# Sheet1.net
KiCad netlist of a schematic drawn in Altium Designer
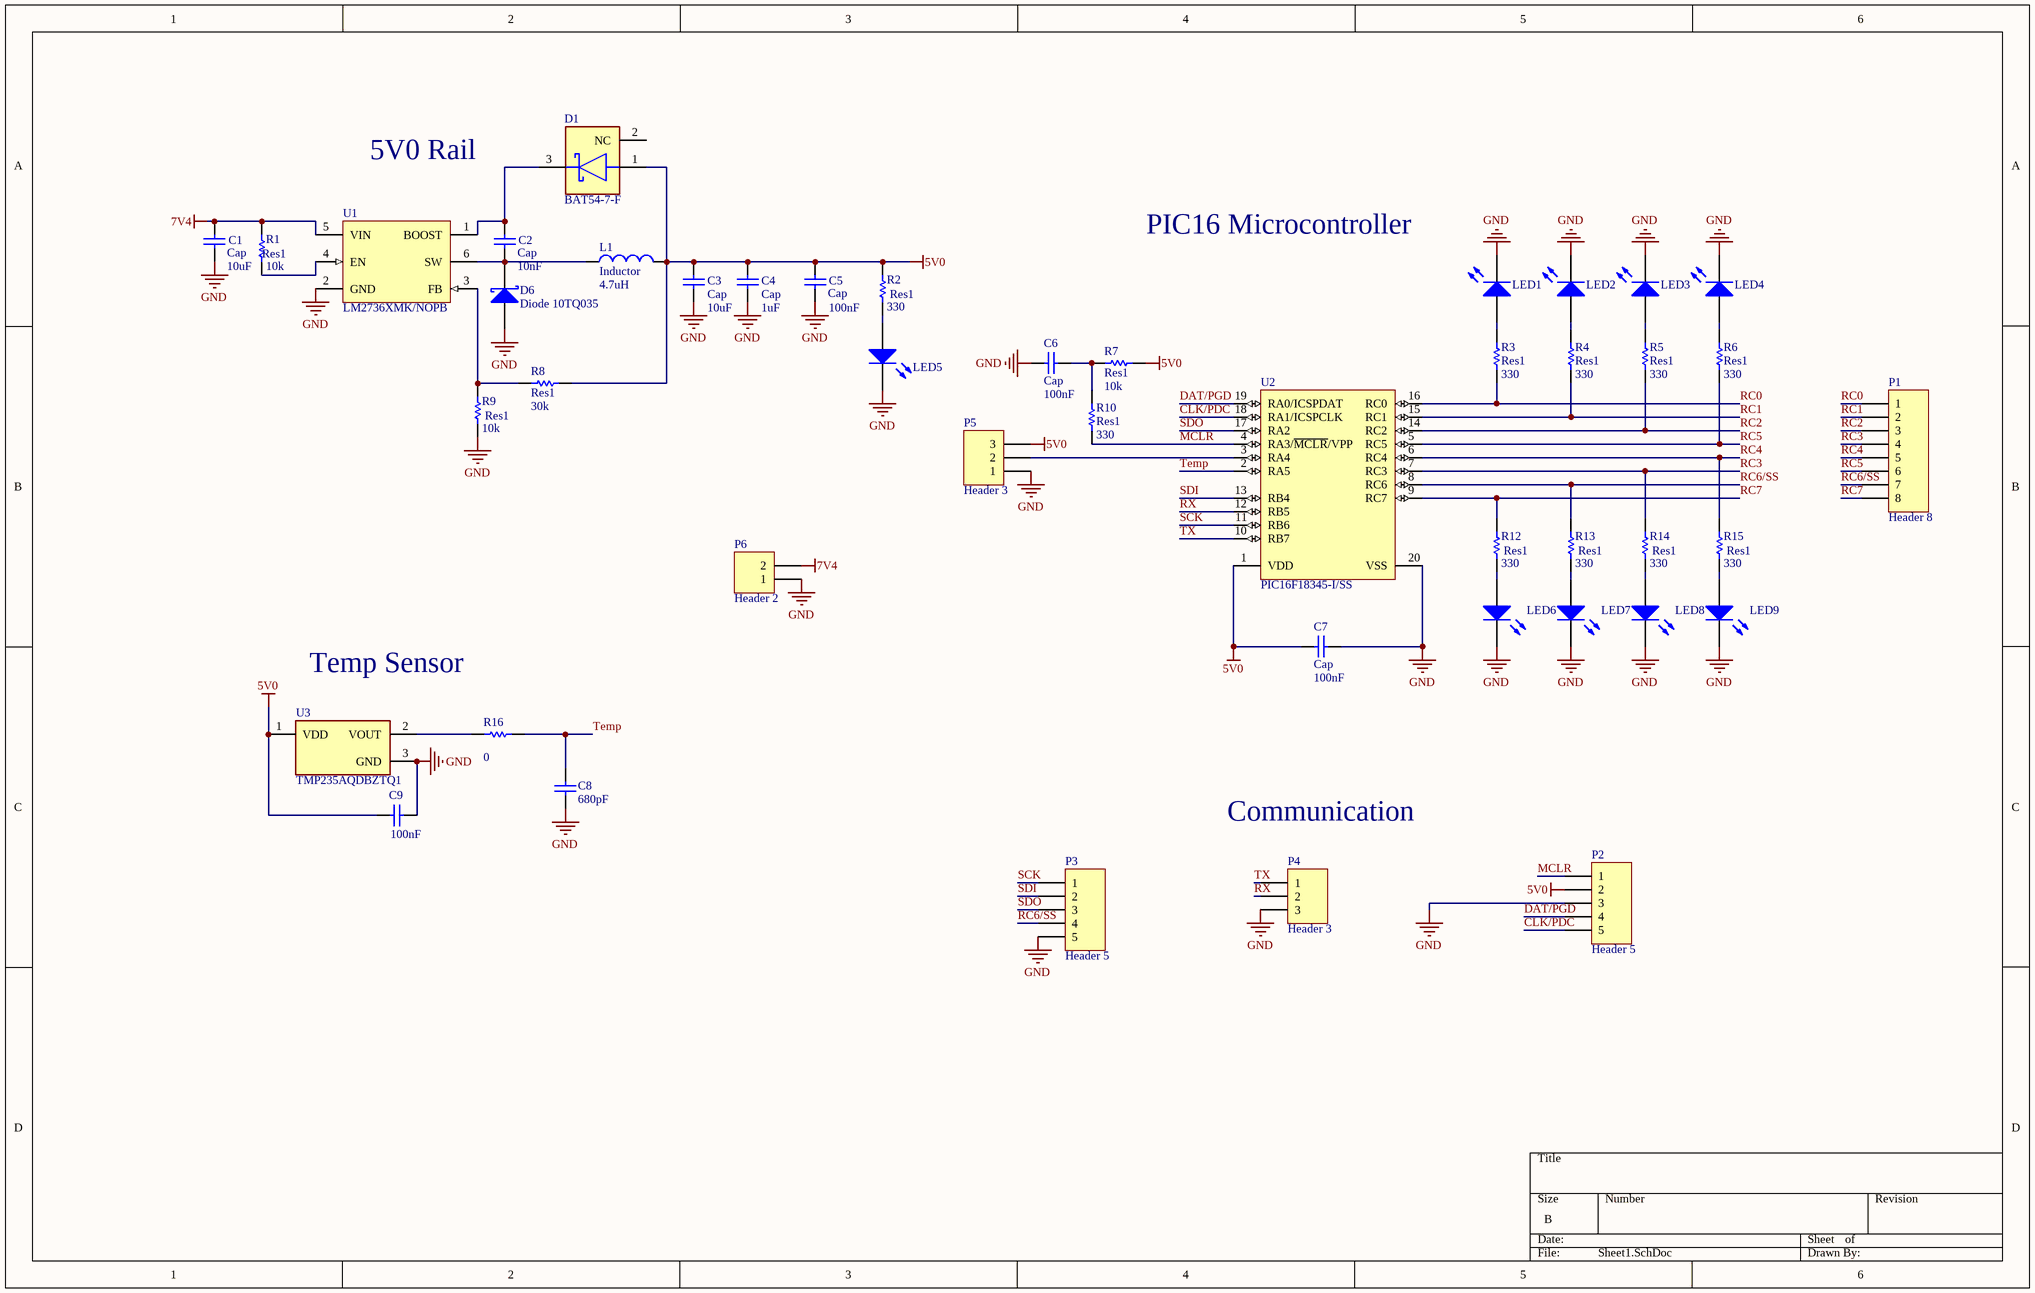
[diagram p0: Sheet1.SchDoc]

(export (version "E")
  (design (tool "Eeschema 10.0.6"))
  (components
    (comp (ref "C1")
      (value "Cap")
      (footprint "6-0805_M")
      (description "Capacitor")
      (fields (field (name "ALTIUM_VALUE") "10uF") (field (name "PUBLISHER") "Altium Limited"))
      (libsource (lib "Miscellaneous Devices") (part "Cap"))
    )
    (comp (ref "C2")
      (value "Cap")
      (footprint "6-0805_M")
      (description "Capacitor")
      (fields (field (name "ALTIUM_VALUE") "10nF") (field (name "PUBLISHER") "Altium Limited"))
      (libsource (lib "Miscellaneous Devices") (part "Cap"))
    )
    (comp (ref "C3")
      (value "Cap")
      (footprint "6-0805_M")
      (description "Capacitor")
      (fields (field (name "ALTIUM_VALUE") "10uF") (field (name "PUBLISHER") "Altium Limited"))
      (libsource (lib "Miscellaneous Devices") (part "Cap"))
    )
    (comp (ref "C4")
      (value "Cap")
      (footprint "6-0805_M")
      (description "Capacitor")
      (fields (field (name "ALTIUM_VALUE") "1uF") (field (name "PUBLISHER") "Altium Limited"))
      (libsource (lib "Miscellaneous Devices") (part "Cap"))
    )
    (comp (ref "C5")
      (value "Cap")
      (footprint "6-0805_M")
      (description "Capacitor")
      (fields (field (name "ALTIUM_VALUE") "100nF") (field (name "PUBLISHER") "Altium Limited"))
      (libsource (lib "Miscellaneous Devices") (part "Cap"))
    )
    (comp (ref "C6")
      (value "Cap")
      (footprint "6-0805_M")
      (description "Capacitor")
      (fields (field (name "ALTIUM_VALUE") "100nF") (field (name "PUBLISHER") "Altium Limited"))
      (libsource (lib "Miscellaneous Devices") (part "Cap"))
    )
    (comp (ref "C7")
      (value "Cap")
      (footprint "6-0805_M")
      (description "Capacitor")
      (fields (field (name "ALTIUM_VALUE") "100nF") (field (name "PUBLISHER") "Altium Limited"))
      (libsource (lib "Miscellaneous Devices") (part "Cap"))
    )
    (comp (ref "C8")
      (value "680pF")
      (footprint "6-0805_M")
      (description "Capacitor")
      (fields (field (name "Comment") "Cap") (field (name "PUBLISHER") "Altium Limited"))
      (libsource (lib "Miscellaneous Devices") (part "Cap"))
    )
    (comp (ref "C9")
      (value "100nF")
      (footprint "6-0805_M")
      (description "Capacitor")
      (fields (field (name "Comment") "Cap") (field (name "PUBLISHER") "Altium Limited"))
      (libsource (lib "Miscellaneous Devices") (part "Cap"))
    )
    (comp (ref "D1")
      (value "BAT54-7-F")
      (footprint "FP-SOT23-MFG")
      (description "DIODE SCHOTTKY 30V 200MA SOT23-3")
      (fields
        (field (name "MANUFACTURER") "Diodes Inc.")
        (field (name "OCTOPART") "https://octopart.com/bat54-7-f-diodes+inc.-39681803")
      )
      (libsource (lib "Altium Content Vault") (part "c46c961685e925f3e7b53c7fd0df730"))
    )
    (comp (ref "D6")
      (value "Diode 10TQ035")
      (footprint "CDBA5")
      (description "Schottky Rectifier")
      (fields (field (name "PUBLISHER") "Altium Limited"))
      (libsource (lib "Miscellaneous Devices") (part "Diode 10TQ035"))
    )
    (comp (ref "L1")
      (value "Inductor")
      (footprint "INDC2520X100N")
      (fields (field (name "ALTIUM_VALUE") "4.7uH") (field (name "PUBLISHER") "Altium Limited"))
      (libsource (lib "Miscellaneous Devices") (part "Inductor"))
    )
    (comp (ref "LED1")
      (value "150080BS75000")
      (footprint "0805_A")
      (description "SMD mono-color Chip LED, WL-SMCW, Blue")
      (fields (field (name "MANUFACTURER") "Wuerth Elektronik"))
      (libsource (lib "Altium Content Vault") (part "WE-LED_K1A2-2"))
    )
    (comp (ref "LED2")
      (value "150080BS75000")
      (footprint "0805_A")
      (description "SMD mono-color Chip LED, WL-SMCW, Blue")
      (fields (field (name "MANUFACTURER") "Wuerth Elektronik"))
      (libsource (lib "Altium Content Vault") (part "WE-LED_K1A2-2"))
    )
    (comp (ref "LED3")
      (value "150080BS75000")
      (footprint "0805_A")
      (description "SMD mono-color Chip LED, WL-SMCW, Blue")
      (fields (field (name "MANUFACTURER") "Wuerth Elektronik"))
      (libsource (lib "Altium Content Vault") (part "WE-LED_K1A2-2"))
    )
    (comp (ref "LED4")
      (value "150080BS75000")
      (footprint "0805_A")
      (description "SMD mono-color Chip LED, WL-SMCW, Blue")
      (fields (field (name "MANUFACTURER") "Wuerth Elektronik"))
      (libsource (lib "Altium Content Vault") (part "WE-LED_K1A2-2"))
    )
    (comp (ref "LED5")
      (value "150080BS75000")
      (footprint "0805_A")
      (description "SMD mono-color Chip LED, WL-SMCW, Blue")
      (fields (field (name "MANUFACTURER") "Wuerth Elektronik"))
      (libsource (lib "Altium Content Vault") (part "WE-LED_K1A2-2"))
    )
    (comp (ref "LED6")
      (value "150080BS75000")
      (footprint "0805_A")
      (description "SMD mono-color Chip LED, WL-SMCW, Blue")
      (fields (field (name "MANUFACTURER") "Wuerth Elektronik"))
      (libsource (lib "Altium Content Vault") (part "WE-LED_K1A2-2"))
    )
    (comp (ref "LED7")
      (value "150080BS75000")
      (footprint "0805_A")
      (description "SMD mono-color Chip LED, WL-SMCW, Blue")
      (fields (field (name "MANUFACTURER") "Wuerth Elektronik"))
      (libsource (lib "Altium Content Vault") (part "WE-LED_K1A2-2"))
    )
    (comp (ref "LED8")
      (value "150080BS75000")
      (footprint "0805_A")
      (description "SMD mono-color Chip LED, WL-SMCW, Blue")
      (fields (field (name "MANUFACTURER") "Wuerth Elektronik"))
      (libsource (lib "Altium Content Vault") (part "WE-LED_K1A2-2"))
    )
    (comp (ref "LED9")
      (value "150080BS75000")
      (footprint "0805_A")
      (description "SMD mono-color Chip LED, WL-SMCW, Blue")
      (fields (field (name "MANUFACTURER") "Wuerth Elektronik"))
      (libsource (lib "Altium Content Vault") (part "WE-LED_K1A2-2"))
    )
    (comp (ref "P1")
      (value "Header 8")
      (footprint "HDR1X8")
      (description "Header, 8-Pin")
      (fields (field (name "PUBLISHER") "Altium Limited"))
      (libsource (lib "Miscellaneous Connectors") (part "Header 8"))
    )
    (comp (ref "P2")
      (value "Header 5")
      (footprint "HDR1X5")
      (description "Header, 5-Pin")
      (fields (field (name "PUBLISHER") "Altium Limited"))
      (libsource (lib "Miscellaneous Connectors") (part "Header 5"))
    )
    (comp (ref "P3")
      (value "Header 5")
      (footprint "HDR1X5")
      (description "Header, 5-Pin")
      (fields (field (name "PUBLISHER") "Altium Limited"))
      (libsource (lib "Miscellaneous Connectors") (part "Header 5"))
    )
    (comp (ref "P4")
      (value "Header 3")
      (footprint "HDR1X3")
      (description "Header, 3-Pin")
      (fields (field (name "PUBLISHER") "Altium Limited"))
      (libsource (lib "") (part "Header 3_1"))
    )
    (comp (ref "P5")
      (value "Header 3")
      (footprint "HDR1X3")
      (description "Header, 3-Pin")
      (fields (field (name "PUBLISHER") "Altium Limited"))
      (libsource (lib "Miscellaneous Connectors") (part "Header 3"))
    )
    (comp (ref "P6")
      (value "Header 2")
      (footprint "HDR1X2")
      (description "Header, 2-Pin")
      (fields (field (name "PUBLISHER") "Altium Limited"))
      (libsource (lib "Miscellaneous Connectors") (part "Header 2"))
    )
    (comp (ref "R1")
      (value "Res1")
      (footprint "6-0805_M")
      (description "Resistor")
      (fields (field (name "ALTIUM_VALUE") "10k") (field (name "PUBLISHER") "Altium Limited"))
      (libsource (lib "Miscellaneous Devices") (part "Res1"))
    )
    (comp (ref "R2")
      (value "Res1")
      (footprint "6-0805_M")
      (description "Resistor")
      (fields (field (name "ALTIUM_VALUE") "330") (field (name "PUBLISHER") "Altium Limited"))
      (libsource (lib "Miscellaneous Devices") (part "Res1"))
    )
    (comp (ref "R3")
      (value "Res1")
      (footprint "6-0805_M")
      (description "Resistor")
      (fields (field (name "ALTIUM_VALUE") "330") (field (name "PUBLISHER") "Altium Limited"))
      (libsource (lib "Miscellaneous Devices") (part "Res1"))
    )
    (comp (ref "R4")
      (value "Res1")
      (footprint "6-0805_M")
      (description "Resistor")
      (fields (field (name "ALTIUM_VALUE") "330") (field (name "PUBLISHER") "Altium Limited"))
      (libsource (lib "Miscellaneous Devices") (part "Res1"))
    )
    (comp (ref "R5")
      (value "Res1")
      (footprint "6-0805_M")
      (description "Resistor")
      (fields (field (name "ALTIUM_VALUE") "330") (field (name "PUBLISHER") "Altium Limited"))
      (libsource (lib "Miscellaneous Devices") (part "Res1"))
    )
    (comp (ref "R6")
      (value "Res1")
      (footprint "6-0805_M")
      (description "Resistor")
      (fields (field (name "ALTIUM_VALUE") "330") (field (name "PUBLISHER") "Altium Limited"))
      (libsource (lib "Miscellaneous Devices") (part "Res1"))
    )
    (comp (ref "R7")
      (value "Res1")
      (footprint "6-0805_M")
      (description "Resistor")
      (fields (field (name "ALTIUM_VALUE") "10k") (field (name "PUBLISHER") "Altium Limited"))
      (libsource (lib "Miscellaneous Devices") (part "Res1"))
    )
    (comp (ref "R8")
      (value "Res1")
      (footprint "6-0805_M")
      (description "Resistor")
      (fields (field (name "ALTIUM_VALUE") "30k") (field (name "PUBLISHER") "Altium Limited"))
      (libsource (lib "Miscellaneous Devices") (part "Res1"))
    )
    (comp (ref "R9")
      (value "Res1")
      (footprint "6-0805_M")
      (description "Resistor")
      (fields (field (name "ALTIUM_VALUE") "10k") (field (name "PUBLISHER") "Altium Limited"))
      (libsource (lib "Miscellaneous Devices") (part "Res1"))
    )
    (comp (ref "R10")
      (value "Res1")
      (footprint "6-0805_M")
      (description "Resistor")
      (fields (field (name "ALTIUM_VALUE") "330") (field (name "PUBLISHER") "Altium Limited"))
      (libsource (lib "Miscellaneous Devices") (part "Res1"))
    )
    (comp (ref "R12")
      (value "Res1")
      (footprint "6-0805_M")
      (description "Resistor")
      (fields (field (name "ALTIUM_VALUE") "330") (field (name "PUBLISHER") "Altium Limited"))
      (libsource (lib "Miscellaneous Devices") (part "Res1"))
    )
    (comp (ref "R13")
      (value "Res1")
      (footprint "6-0805_M")
      (description "Resistor")
      (fields (field (name "ALTIUM_VALUE") "330") (field (name "PUBLISHER") "Altium Limited"))
      (libsource (lib "Miscellaneous Devices") (part "Res1"))
    )
    (comp (ref "R14")
      (value "Res1")
      (footprint "6-0805_M")
      (description "Resistor")
      (fields (field (name "ALTIUM_VALUE") "330") (field (name "PUBLISHER") "Altium Limited"))
      (libsource (lib "Miscellaneous Devices") (part "Res1"))
    )
    (comp (ref "R15")
      (value "Res1")
      (footprint "6-0805_M")
      (description "Resistor")
      (fields (field (name "ALTIUM_VALUE") "330") (field (name "PUBLISHER") "Altium Limited"))
      (libsource (lib "Miscellaneous Devices") (part "Res1"))
    )
    (comp (ref "R16")
      (value "0")
      (footprint "6-0805_M")
      (description "Resistor")
      (fields (field (name "Comment") "Res1") (field (name "PUBLISHER") "Altium Limited"))
      (libsource (lib "Miscellaneous Devices") (part "Res1"))
    )
    (comp (ref "U1")
      (value "LM2736XMK/NOPB")
      (footprint "DDC0006A_L")
      (description "750mA Load Step-Down DC-DC Regulator, 6-pin Tiny SOT23, Pb-Free")
      (fields (field (name "MANUFACTURER") "Texas Instruments"))
      (libsource (lib "Altium Content Vault") (part "PM-DCDC-LM2736MK"))
    )
    (comp (ref "U2")
      (value "PIC16F18345-I/SS")
      (footprint "MCHP-SS-20_V")
      (fields (field (name "MANUFACTURER") "Microchip-Technology"))
      (libsource (lib "Altium Content Vault") (part "MCHP-PIC16XF18345-20"))
    )
    (comp (ref "U3")
      (value "TMP235AQDBZTQ1")
      (footprint "FP-DBZ0003A-MFG")
      (description "LOW-POWER HIGH-ACCURACY ANALOG O")
      (fields
        (field (name "MANUFACTURER") "Texas Instruments")
        (field (name "MANUFACTURER PART NUMBER") "TMP235A2DBZR")
      )
      (libsource (lib "Altium Content Vault") (part "1212246baba8f64ab0dd7b63bd818eb"))
    )
  )
  (nets
    (net (code "1") (name "/CLK{slash}PDC") (class "Default")
      (node (ref "P2") (pin "5") (pinfunction "5_5") (pintype "passive"))
      (node (ref "U2") (pin "18") (pinfunction "RA1/ICSPCLK_18") (pintype "bidirectional"))
    )
    (net (code "2") (name "/DAT{slash}PGD") (class "Default")
      (node (ref "P2") (pin "4") (pinfunction "4_4") (pintype "passive"))
      (node (ref "U2") (pin "19") (pinfunction "RA0/ICSPDAT_19") (pintype "bidirectional"))
    )
    (net (code "3") (name "/MCLR") (class "Default")
      (node (ref "P2") (pin "1") (pinfunction "1_1") (pintype "passive"))
      (node (ref "R10") (pin "1") (pinfunction "1_1") (pintype "passive"))
      (node (ref "U2") (pin "4") (pinfunction "RA3/~{MCLR}/VPP_4") (pintype "bidirectional"))
    )
    (net (code "4") (name "/RC0") (class "Default")
      (node (ref "P1") (pin "1") (pinfunction "1_1") (pintype "passive"))
      (node (ref "R3") (pin "2") (pinfunction "2_2") (pintype "passive"))
      (node (ref "U2") (pin "16") (pinfunction "RC0_16") (pintype "bidirectional"))
    )
    (net (code "5") (name "/RC1") (class "Default")
      (node (ref "P1") (pin "2") (pinfunction "2_2") (pintype "passive"))
      (node (ref "R4") (pin "2") (pinfunction "2_2") (pintype "passive"))
      (node (ref "U2") (pin "15") (pinfunction "RC1_15") (pintype "bidirectional"))
    )
    (net (code "6") (name "/RC2") (class "Default")
      (node (ref "P1") (pin "3") (pinfunction "3_3") (pintype "passive"))
      (node (ref "R5") (pin "2") (pinfunction "2_2") (pintype "passive"))
      (node (ref "U2") (pin "14") (pinfunction "RC2_14") (pintype "bidirectional"))
    )
    (net (code "7") (name "/RC3") (class "Default")
      (node (ref "P1") (pin "4") (pinfunction "4_4") (pintype "passive"))
      (node (ref "R14") (pin "2") (pinfunction "2_2") (pintype "passive"))
      (node (ref "U2") (pin "7") (pinfunction "RC3_7") (pintype "bidirectional"))
    )
    (net (code "8") (name "/RC4") (class "Default")
      (node (ref "P1") (pin "5") (pinfunction "5_5") (pintype "passive"))
      (node (ref "R15") (pin "2") (pinfunction "2_2") (pintype "passive"))
      (node (ref "U2") (pin "6") (pinfunction "RC4_6") (pintype "bidirectional"))
    )
    (net (code "9") (name "/RC5") (class "Default")
      (node (ref "P1") (pin "6") (pinfunction "6_6") (pintype "passive"))
      (node (ref "R6") (pin "2") (pinfunction "2_2") (pintype "passive"))
      (node (ref "U2") (pin "5") (pinfunction "RC5_5") (pintype "bidirectional"))
    )
    (net (code "10") (name "/RC6{slash}SS") (class "Default")
      (node (ref "P1") (pin "7") (pinfunction "7_7") (pintype "passive"))
      (node (ref "P3") (pin "4") (pinfunction "4_4") (pintype "passive"))
      (node (ref "R13") (pin "2") (pinfunction "2_2") (pintype "passive"))
      (node (ref "U2") (pin "8") (pinfunction "RC6_8") (pintype "bidirectional"))
    )
    (net (code "11") (name "/RC7") (class "Default")
      (node (ref "P1") (pin "8") (pinfunction "8_8") (pintype "passive"))
      (node (ref "R12") (pin "2") (pinfunction "2_2") (pintype "passive"))
      (node (ref "U2") (pin "9") (pinfunction "RC7_9") (pintype "bidirectional"))
    )
    (net (code "12") (name "/RX") (class "Default")
      (node (ref "P4") (pin "2") (pinfunction "2_2") (pintype "passive"))
      (node (ref "U2") (pin "12") (pinfunction "RB5_12") (pintype "bidirectional"))
    )
    (net (code "13") (name "/SCK") (class "Default")
      (node (ref "P3") (pin "1") (pinfunction "1_1") (pintype "passive"))
      (node (ref "U2") (pin "11") (pinfunction "RB6_11") (pintype "bidirectional"))
    )
    (net (code "14") (name "/SDI") (class "Default")
      (node (ref "P3") (pin "2") (pinfunction "2_2") (pintype "passive"))
      (node (ref "U2") (pin "13") (pinfunction "RB4_13") (pintype "bidirectional"))
    )
    (net (code "15") (name "/SDO") (class "Default")
      (node (ref "P3") (pin "3") (pinfunction "3_3") (pintype "passive"))
      (node (ref "U2") (pin "17") (pinfunction "RA2_17") (pintype "bidirectional"))
    )
    (net (code "16") (name "/TX") (class "Default")
      (node (ref "P4") (pin "1") (pinfunction "1_1") (pintype "passive"))
      (node (ref "U2") (pin "10") (pinfunction "RB7_10") (pintype "bidirectional"))
    )
    (net (code "17") (name "/Temp") (class "Default")
      (node (ref "C8") (pin "1") (pinfunction "1_1") (pintype "passive"))
      (node (ref "R16") (pin "2") (pinfunction "2_2") (pintype "passive"))
      (node (ref "U2") (pin "2") (pinfunction "RA5_2") (pintype "bidirectional"))
    )
    (net (code "18") (name "5V0") (class "Default")
      (node (ref "C3") (pin "2") (pinfunction "2_2") (pintype "passive"))
      (node (ref "C4") (pin "2") (pinfunction "2_2") (pintype "passive"))
      (node (ref "C5") (pin "2") (pinfunction "2_2") (pintype "passive"))
      (node (ref "C7") (pin "2") (pinfunction "2_2") (pintype "passive"))
      (node (ref "C9") (pin "1") (pinfunction "1_1") (pintype "passive"))
      (node (ref "D1") (pin "1") (pinfunction "A_1") (pintype "passive"))
      (node (ref "L1") (pin "2") (pinfunction "2_2") (pintype "passive"))
      (node (ref "P2") (pin "2") (pinfunction "2_2") (pintype "passive"))
      (node (ref "P5") (pin "3") (pinfunction "3_3") (pintype "passive"))
      (node (ref "R2") (pin "2") (pinfunction "2_2") (pintype "passive"))
      (node (ref "R7") (pin "2") (pinfunction "2_2") (pintype "passive"))
      (node (ref "R8") (pin "1") (pinfunction "1_1") (pintype "passive"))
      (node (ref "U2") (pin "1") (pinfunction "VDD_1") (pintype "power_in"))
      (node (ref "U3") (pin "1") (pinfunction "VDD_1") (pintype "power_in"))
    )
    (net (code "19") (name "7V4") (class "Default")
      (node (ref "C1") (pin "2") (pinfunction "2_2") (pintype "passive"))
      (node (ref "P6") (pin "2") (pinfunction "2_2") (pintype "passive"))
      (node (ref "R1") (pin "2") (pinfunction "2_2") (pintype "passive"))
      (node (ref "U1") (pin "5") (pinfunction "VIN_5") (pintype "power_in"))
    )
    (net (code "20") (name "GND") (class "Default")
      (node (ref "C1") (pin "1") (pinfunction "1_1") (pintype "passive"))
      (node (ref "C3") (pin "1") (pinfunction "1_1") (pintype "passive"))
      (node (ref "C4") (pin "1") (pinfunction "1_1") (pintype "passive"))
      (node (ref "C5") (pin "1") (pinfunction "1_1") (pintype "passive"))
      (node (ref "C6") (pin "2") (pinfunction "2_2") (pintype "passive"))
      (node (ref "C7") (pin "1") (pinfunction "1_1") (pintype "passive"))
      (node (ref "C8") (pin "2") (pinfunction "2_2") (pintype "passive"))
      (node (ref "C9") (pin "2") (pinfunction "2_2") (pintype "passive"))
      (node (ref "D6") (pin "3") (pinfunction "A_3") (pintype "passive"))
      (node (ref "LED1") (pin "1") (pinfunction "K_1") (pintype "passive"))
      (node (ref "LED2") (pin "1") (pinfunction "K_1") (pintype "passive"))
      (node (ref "LED3") (pin "1") (pinfunction "K_1") (pintype "passive"))
      (node (ref "LED4") (pin "1") (pinfunction "K_1") (pintype "passive"))
      (node (ref "LED5") (pin "1") (pinfunction "K_1") (pintype "passive"))
      (node (ref "LED6") (pin "1") (pinfunction "K_1") (pintype "passive"))
      (node (ref "LED7") (pin "1") (pinfunction "K_1") (pintype "passive"))
      (node (ref "LED8") (pin "1") (pinfunction "K_1") (pintype "passive"))
      (node (ref "LED9") (pin "1") (pinfunction "K_1") (pintype "passive"))
      (node (ref "P2") (pin "3") (pinfunction "3_3") (pintype "passive"))
      (node (ref "P3") (pin "5") (pinfunction "5_5") (pintype "passive"))
      (node (ref "P4") (pin "3") (pinfunction "3_3") (pintype "passive"))
      (node (ref "P5") (pin "1") (pinfunction "1_1") (pintype "passive"))
      (node (ref "P6") (pin "1") (pinfunction "1_1") (pintype "passive"))
      (node (ref "R9") (pin "1") (pinfunction "1_1") (pintype "passive"))
      (node (ref "U1") (pin "2") (pinfunction "GND_2") (pintype "power_in"))
      (node (ref "U2") (pin "20") (pinfunction "VSS_20") (pintype "power_in"))
      (node (ref "U3") (pin "3") (pinfunction "GND_3") (pintype "power_in"))
    )
    (net (code "21") (name "Net-(C6-Pad1)") (class "Default")
      (node (ref "C6") (pin "1") (pinfunction "1_1") (pintype "passive"))
      (node (ref "R10") (pin "2") (pinfunction "2_2") (pintype "passive"))
      (node (ref "R7") (pin "1") (pinfunction "1_1") (pintype "passive"))
    )
    (net (code "22") (name "Net-(D1-C)") (class "Default")
      (node (ref "C2") (pin "2") (pinfunction "2_2") (pintype "passive"))
      (node (ref "D1") (pin "3") (pinfunction "C_3") (pintype "passive"))
      (node (ref "U1") (pin "1") (pinfunction "BOOST_1") (pintype "passive"))
    )
    (net (code "23") (name "Net-(D6-K)") (class "Default")
      (node (ref "C2") (pin "1") (pinfunction "1_1") (pintype "passive"))
      (node (ref "D6") (pin "1") (pinfunction "K_1") (pintype "passive"))
      (node (ref "L1") (pin "1") (pinfunction "1_1") (pintype "passive"))
      (node (ref "U1") (pin "6") (pinfunction "SW_6") (pintype "power_in"))
    )
    (net (code "24") (name "Net-(LED1-A)") (class "Default")
      (node (ref "LED1") (pin "2") (pinfunction "A_2") (pintype "passive"))
      (node (ref "R3") (pin "1") (pinfunction "1_1") (pintype "passive"))
    )
    (net (code "25") (name "Net-(LED2-A)") (class "Default")
      (node (ref "LED2") (pin "2") (pinfunction "A_2") (pintype "passive"))
      (node (ref "R4") (pin "1") (pinfunction "1_1") (pintype "passive"))
    )
    (net (code "26") (name "Net-(LED3-A)") (class "Default")
      (node (ref "LED3") (pin "2") (pinfunction "A_2") (pintype "passive"))
      (node (ref "R5") (pin "1") (pinfunction "1_1") (pintype "passive"))
    )
    (net (code "27") (name "Net-(LED4-A)") (class "Default")
      (node (ref "LED4") (pin "2") (pinfunction "A_2") (pintype "passive"))
      (node (ref "R6") (pin "1") (pinfunction "1_1") (pintype "passive"))
    )
    (net (code "28") (name "Net-(LED5-A)") (class "Default")
      (node (ref "LED5") (pin "2") (pinfunction "A_2") (pintype "passive"))
      (node (ref "R2") (pin "1") (pinfunction "1_1") (pintype "passive"))
    )
    (net (code "29") (name "Net-(LED6-A)") (class "Default")
      (node (ref "LED6") (pin "2") (pinfunction "A_2") (pintype "passive"))
      (node (ref "R12") (pin "1") (pinfunction "1_1") (pintype "passive"))
    )
    (net (code "30") (name "Net-(LED7-A)") (class "Default")
      (node (ref "LED7") (pin "2") (pinfunction "A_2") (pintype "passive"))
      (node (ref "R13") (pin "1") (pinfunction "1_1") (pintype "passive"))
    )
    (net (code "31") (name "Net-(LED8-A)") (class "Default")
      (node (ref "LED8") (pin "2") (pinfunction "A_2") (pintype "passive"))
      (node (ref "R14") (pin "1") (pinfunction "1_1") (pintype "passive"))
    )
    (net (code "32") (name "Net-(LED9-A)") (class "Default")
      (node (ref "LED9") (pin "2") (pinfunction "A_2") (pintype "passive"))
      (node (ref "R15") (pin "1") (pinfunction "1_1") (pintype "passive"))
    )
    (net (code "33") (name "Net-(U1-EN)") (class "Default")
      (node (ref "R1") (pin "1") (pinfunction "1_1") (pintype "passive"))
      (node (ref "U1") (pin "4") (pinfunction "EN_4") (pintype "input"))
    )
    (net (code "34") (name "Net-(U1-FB)") (class "Default")
      (node (ref "R8") (pin "2") (pinfunction "2_2") (pintype "passive"))
      (node (ref "R9") (pin "2") (pinfunction "2_2") (pintype "passive"))
      (node (ref "U1") (pin "3") (pinfunction "FB_3") (pintype "input"))
    )
    (net (code "35") (name "Net-(U2-RA4)") (class "Default")
      (node (ref "P5") (pin "2") (pinfunction "2_2") (pintype "passive"))
      (node (ref "U2") (pin "3") (pinfunction "RA4_3") (pintype "bidirectional"))
    )
    (net (code "36") (name "Net-(U3-VOUT)") (class "Default")
      (node (ref "R16") (pin "1") (pinfunction "1_1") (pintype "passive"))
      (node (ref "U3") (pin "2") (pinfunction "VOUT_2") (pintype "passive"))
    )
    (net (code "37") (name "unconnected-(D1-NC-Pad2)") (class "Default")
      (node (ref "D1") (pin "2") (pinfunction "NC_2") (pintype "passive"))
    )
  )
)
